# ESP32_C3.net
KiCad netlist of a schematic drawn in Altium Designer
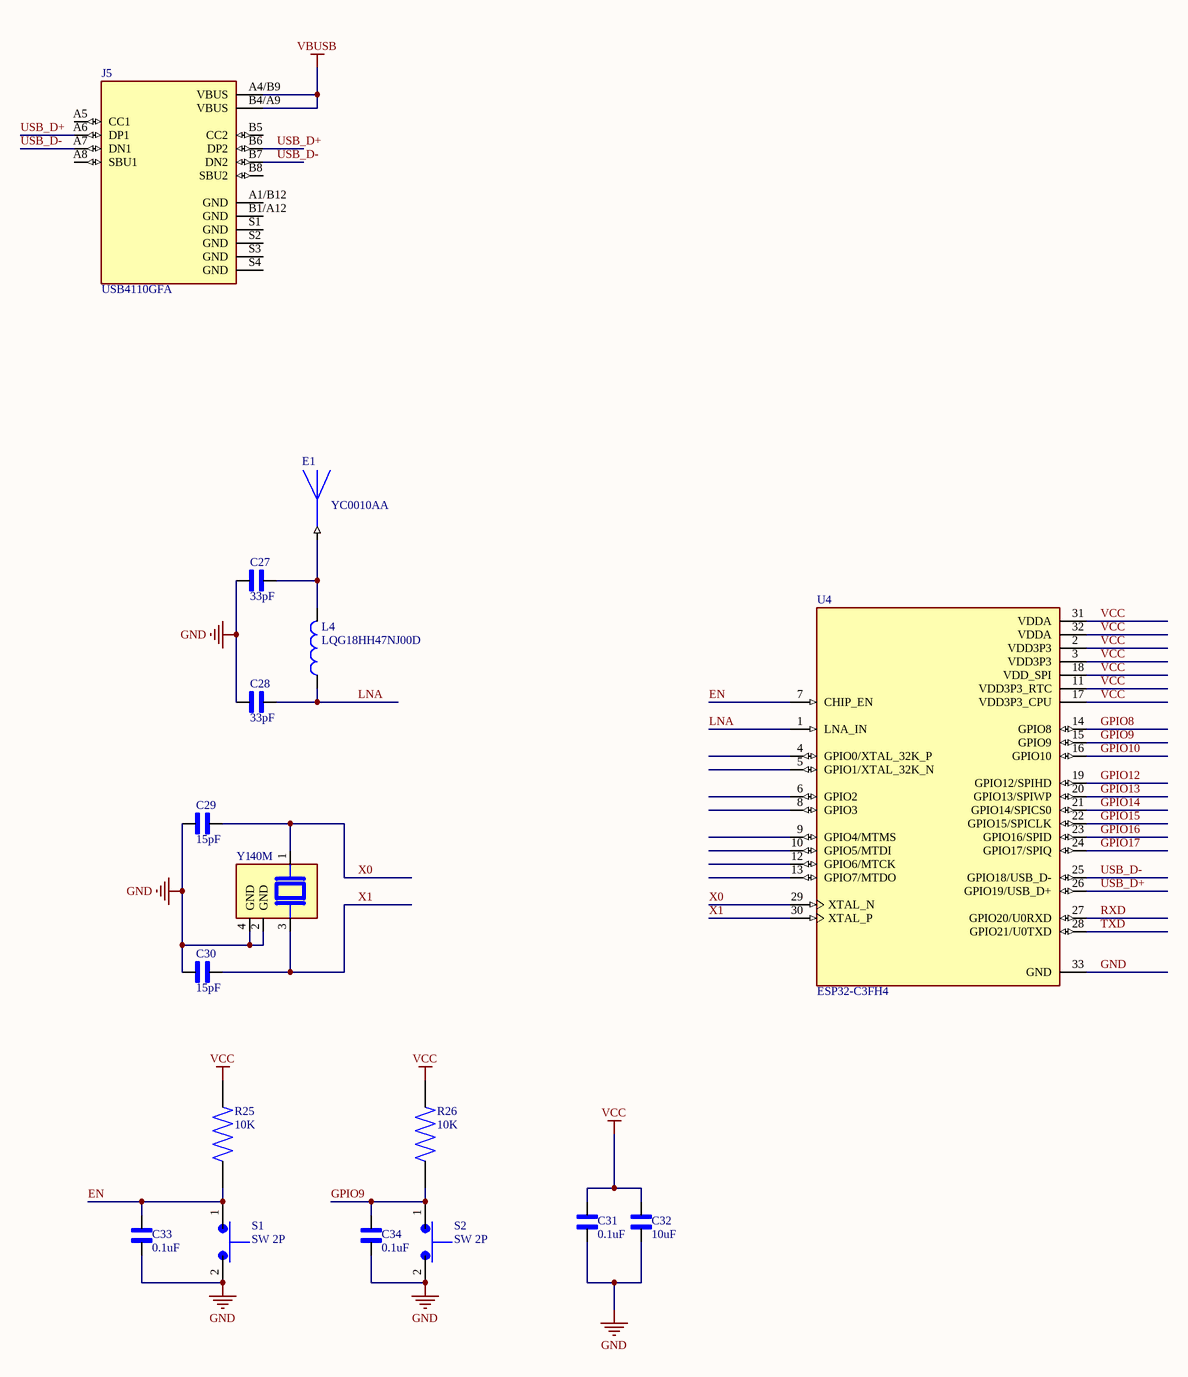
[diagram p0: ESP32 C3.SchDoc]

(export (version "E")
  (design (tool "Eeschema 10.0.6"))
  (components
    (comp (ref "C27")
      (value "33pF")
      (footprint "CAPC2012X140N")
      (fields
        (field (name "MF") "{'manufacturer': u'Samsung Electro-Mechanics'}")
        (field (name "MP") "CL21A226MQQNNNG")
      )
      (libsource (lib "") (part "CL21A226MQQNNNG_1"))
    )
    (comp (ref "C28")
      (value "33pF")
      (footprint "CAPC2012X140N")
      (fields
        (field (name "MF") "{'manufacturer': u'Samsung Electro-Mechanics'}")
        (field (name "MP") "CL21A226MQQNNNG")
      )
      (libsource (lib "") (part "CL21A226MQQNNNG_1"))
    )
    (comp (ref "C29")
      (value "15pF")
      (footprint "CAPC2012X140N")
      (fields
        (field (name "MF") "{'manufacturer': u'Samsung Electro-Mechanics'}")
        (field (name "MP") "CL21A226MQQNNNG")
      )
      (libsource (lib "") (part "CL21A226MQQNNNG_2"))
    )
    (comp (ref "C30")
      (value "15pF")
      (footprint "CAPC2012X140N")
      (fields
        (field (name "MF") "{'manufacturer': u'Samsung Electro-Mechanics'}")
        (field (name "MP") "CL21A226MQQNNNG")
      )
      (libsource (lib "") (part "CL21A226MQQNNNG_1"))
    )
    (comp (ref "C31")
      (value "0.1uF")
      (footprint "CAPC2012X140N")
      (fields
        (field (name "MF") "{'manufacturer': u'Samsung Electro-Mechanics'}")
        (field (name "MP") "CL21A226MQQNNNG")
      )
      (libsource (lib "SnapEDA_Library") (part "CL21A226MQQNNNG"))
    )
    (comp (ref "C32")
      (value "10uF")
      (footprint "CAPC2012X140N")
      (fields
        (field (name "MF") "{'manufacturer': u'Samsung Electro-Mechanics'}")
        (field (name "MP") "CL21A226MQQNNNG")
      )
      (libsource (lib "SnapEDA_Library") (part "CL21A226MQQNNNG"))
    )
    (comp (ref "C33")
      (value "0.1uF")
      (footprint "CAPC2012X140N")
      (fields
        (field (name "MF") "{'manufacturer': u'Samsung Electro-Mechanics'}")
        (field (name "MP") "CL21A226MQQNNNG")
      )
      (libsource (lib "SnapEDA_Library") (part "CL21A226MQQNNNG"))
    )
    (comp (ref "C34")
      (value "0.1uF")
      (footprint "CAPC2012X140N")
      (fields
        (field (name "MF") "{'manufacturer': u'Samsung Electro-Mechanics'}")
        (field (name "MP") "CL21A226MQQNNNG")
      )
      (libsource (lib "SnapEDA_Library") (part "CL21A226MQQNNNG"))
    )
    (comp (ref "E1")
      (value "YC0010AA")
      (footprint "XCVR_YC0010AA")
      (description "2400 ~ 2500MHz, Wi-Fiï¼ˆBTï¼‰, 5.2*2.0*1.2mm,ceramic SMD Antenna")
      (fields (field (name "MF") "Quectel"))
      (libsource (lib "YC0010AA") (part "YC0010AA"))
    )
    (comp (ref "J5")
      (value "USB4110GFA")
      (footprint "GCT_USB4110GFA")
      (fields (field (name "MF") "Global Connector Technology"))
      (libsource (lib "USB4110GFA") (part "USB4110GFA"))
    )
    (comp (ref "L4")
      (value "LQG18HH47NJ00D")
      (footprint "INDC1608X95N")
      (fields (field (name "MF") "{'manufacturer': u'Murata Electronics'}"))
      (libsource (lib "SnapEDA_Library") (part "LQG18HH47NJ00D"))
    )
    (comp (ref "R25")
      (value "10K")
      (footprint "RESC2012X65N")
      (fields (field (name "MF") "{'manufacturer': u'Rohm'}") (field (name "MP") "MCR10EZHJ103"))
      (libsource (lib "SnapEDA_Library") (part "MCR10EZHJ103"))
    )
    (comp (ref "R26")
      (value "10K")
      (footprint "RESC2012X65N")
      (fields (field (name "MF") "{'manufacturer': u'Rohm'}") (field (name "MP") "MCR10EZHJ103"))
      (libsource (lib "SnapEDA_Library") (part "MCR10EZHJ103"))
    )
    (comp (ref "S1")
      (value "SW 2P")
      (footprint "TS10-63-26-BE-250-SMT-TR:SW_TS10-63-26-BE-250-SMT-TR")
      (fields
        (field (name "MF") "{'manufacturer': u'Same Sky'}")
        (field (name "MP") "TS10-63-26-BE-250-SMT-TR")
      )
      (libsource (lib "TS10-63-26-BE-250-SMT-TR") (part "TS10-63-26-BE-250-SMT-TR"))
    )
    (comp (ref "S2")
      (value "SW 2P")
      (footprint "TS10-63-26-BE-250-SMT-TR:SW_TS10-63-26-BE-250-SMT-TR")
      (fields
        (field (name "MF") "{'manufacturer': u'Same Sky'}")
        (field (name "MP") "TS10-63-26-BE-250-SMT-TR")
      )
      (libsource (lib "TS10-63-26-BE-250-SMT-TR") (part "TS10-63-26-BE-250-SMT-TR"))
    )
    (comp (ref "U4")
      (value "ESP32-C3FH4")
      (footprint "QFN50P500X500X90-33N")
      (fields (field (name "MF") "{'manufacturer': u'Espressif Systems'}"))
      (libsource (lib "SnapEDA_Library") (part "ESP32-C3FH4"))
    )
    (comp (ref "Y1")
      (value "40M")
      (footprint "XTAL_ABM12-26.000MHZ-B2X-T3")
      (fields
        (field (name "MF") "{'manufacturer': u'Abracon LLC'}")
        (field (name "MP") "ABM12-26.000MHZ-B2X-T3")
      )
      (libsource (lib "SnapEDA_Library") (part "ABM12-26.000MHZ-B2X-T3"))
    )
  )
  (nets
    (net (code "1") (name "/EN") (class "Default")
      (node (ref "C33") (pin "2") (pinfunction "2_2") (pintype "passive"))
      (node (ref "R25") (pin "1") (pinfunction "1_1") (pintype "passive"))
      (node (ref "S1") (pin "1") (pinfunction "1_1") (pintype "passive"))
      (node (ref "U4") (pin "7") (pinfunction "CHIP_EN_7") (pintype "input"))
    )
    (net (code "2") (name "/GPIO8") (class "Default")
      (node (ref "U4") (pin "14") (pinfunction "GPIO8_14") (pintype "bidirectional"))
    )
    (net (code "3") (name "/GPIO9") (class "Default")
      (node (ref "C34") (pin "2") (pinfunction "2_2") (pintype "passive"))
      (node (ref "R26") (pin "1") (pinfunction "1_1") (pintype "passive"))
      (node (ref "S2") (pin "1") (pinfunction "1_1") (pintype "passive"))
      (node (ref "U4") (pin "15") (pinfunction "GPIO9_15") (pintype "bidirectional"))
    )
    (net (code "4") (name "/GPIO10") (class "Default")
      (node (ref "U4") (pin "16") (pinfunction "GPIO10_16") (pintype "bidirectional"))
    )
    (net (code "5") (name "/GPIO12") (class "Default")
      (node (ref "U4") (pin "19") (pinfunction "GPIO12/SPIHD_19") (pintype "bidirectional"))
    )
    (net (code "6") (name "/GPIO13") (class "Default")
      (node (ref "U4") (pin "20") (pinfunction "GPIO13/SPIWP_20") (pintype "bidirectional"))
    )
    (net (code "7") (name "/GPIO14") (class "Default")
      (node (ref "U4") (pin "21") (pinfunction "GPIO14/SPICS0_21") (pintype "bidirectional"))
    )
    (net (code "8") (name "/GPIO15") (class "Default")
      (node (ref "U4") (pin "22") (pinfunction "GPIO15/SPICLK_22") (pintype "bidirectional"))
    )
    (net (code "9") (name "/GPIO16") (class "Default")
      (node (ref "U4") (pin "23") (pinfunction "GPIO16/SPID_23") (pintype "bidirectional"))
    )
    (net (code "10") (name "/GPIO17") (class "Default")
      (node (ref "U4") (pin "24") (pinfunction "GPIO17/SPIQ_24") (pintype "bidirectional"))
    )
    (net (code "11") (name "/LNA") (class "Default")
      (node (ref "C28") (pin "1") (pinfunction "1_1") (pintype "passive"))
      (node (ref "L4") (pin "1") (pinfunction "1_1") (pintype "passive"))
      (node (ref "U4") (pin "1") (pinfunction "LNA_IN_1") (pintype "input"))
    )
    (net (code "12") (name "/RXD") (class "Default")
      (node (ref "U4") (pin "27") (pinfunction "GPIO20/U0RXD_27") (pintype "bidirectional"))
    )
    (net (code "13") (name "/TXD") (class "Default")
      (node (ref "U4") (pin "28") (pinfunction "GPIO21/U0TXD_28") (pintype "bidirectional"))
    )
    (net (code "14") (name "/USB_D+") (class "Default")
      (node (ref "J5") (pin "A6") (pinfunction "DP1_A6") (pintype "bidirectional"))
      (node (ref "J5") (pin "B6") (pinfunction "DP2_B6") (pintype "bidirectional"))
      (node (ref "U4") (pin "26") (pinfunction "GPIO19/USB_D+_26") (pintype "bidirectional"))
    )
    (net (code "15") (name "/USB_D-") (class "Default")
      (node (ref "J5") (pin "A7") (pinfunction "DN1_A7") (pintype "bidirectional"))
      (node (ref "J5") (pin "B7") (pinfunction "DN2_B7") (pintype "bidirectional"))
      (node (ref "U4") (pin "25") (pinfunction "GPIO18/USB_D-_25") (pintype "bidirectional"))
    )
    (net (code "16") (name "/X0") (class "Default")
      (node (ref "C29") (pin "2") (pinfunction "2_2") (pintype "passive"))
      (node (ref "U4") (pin "29") (pinfunction "XTAL_N_29") (pintype "input"))
      (node (ref "Y1") (pin "1") (pinfunction "1_1") (pintype "passive"))
    )
    (net (code "17") (name "/X1") (class "Default")
      (node (ref "C30") (pin "1") (pinfunction "1_1") (pintype "passive"))
      (node (ref "U4") (pin "30") (pinfunction "XTAL_P_30") (pintype "input"))
      (node (ref "Y1") (pin "3") (pinfunction "2_3") (pintype "passive"))
    )
    (net (code "18") (name "GND") (class "Default")
      (node (ref "C27") (pin "2") (pinfunction "2_2") (pintype "passive"))
      (node (ref "C28") (pin "2") (pinfunction "2_2") (pintype "passive"))
      (node (ref "C29") (pin "1") (pinfunction "1_1") (pintype "passive"))
      (node (ref "C30") (pin "2") (pinfunction "2_2") (pintype "passive"))
      (node (ref "C31") (pin "1") (pinfunction "1_1") (pintype "passive"))
      (node (ref "C32") (pin "1") (pinfunction "1_1") (pintype "passive"))
      (node (ref "C33") (pin "1") (pinfunction "1_1") (pintype "passive"))
      (node (ref "C34") (pin "1") (pinfunction "1_1") (pintype "passive"))
      (node (ref "S1") (pin "2") (pinfunction "2_2") (pintype "passive"))
      (node (ref "S2") (pin "2") (pinfunction "2_2") (pintype "passive"))
      (node (ref "U4") (pin "33") (pinfunction "GND_33") (pintype "power_in"))
      (node (ref "Y1") (pin "2") (pinfunction "GND_2") (pintype "power_in"))
      (node (ref "Y1") (pin "4") (pinfunction "GND_4") (pintype "power_in"))
    )
    (net (code "19") (name "Net-(C27-Pad1)") (class "Default")
      (node (ref "C27") (pin "1") (pinfunction "1_1") (pintype "passive"))
      (node (ref "E1") (pin "1") (pinfunction "1_1") (pintype "input"))
      (node (ref "L4") (pin "2") (pinfunction "2_2") (pintype "passive"))
    )
    (net (code "20") (name "VBUSB") (class "Default")
      (node (ref "J5") (pin "A4/B9") (pinfunction "VBUS_A4/B9") (pintype "power_in"))
      (node (ref "J5") (pin "B4/A9") (pinfunction "VBUS_B4/A9") (pintype "power_in"))
    )
    (net (code "21") (name "VCC") (class "Default")
      (node (ref "C31") (pin "2") (pinfunction "2_2") (pintype "passive"))
      (node (ref "C32") (pin "2") (pinfunction "2_2") (pintype "passive"))
      (node (ref "R25") (pin "2") (pinfunction "2_2") (pintype "passive"))
      (node (ref "R26") (pin "2") (pinfunction "2_2") (pintype "passive"))
      (node (ref "U4") (pin "11") (pinfunction "VDD3P3_RTC_11") (pintype "power_in"))
      (node (ref "U4") (pin "17") (pinfunction "VDD3P3_CPU_17") (pintype "power_in"))
      (node (ref "U4") (pin "18") (pinfunction "VDD_SPI_18") (pintype "power_in"))
      (node (ref "U4") (pin "2") (pinfunction "VDD3P3_2") (pintype "power_in"))
      (node (ref "U4") (pin "3") (pinfunction "VDD3P3_3") (pintype "power_in"))
      (node (ref "U4") (pin "31") (pinfunction "VDDA_31") (pintype "power_in"))
      (node (ref "U4") (pin "32") (pinfunction "VDDA_32") (pintype "power_in"))
    )
    (net (code "22") (name "unconnected-(J5-CC1-PadA5)") (class "Default")
      (node (ref "J5") (pin "A5") (pinfunction "CC1_A5") (pintype "bidirectional"))
    )
    (net (code "23") (name "unconnected-(J5-CC2-PadB5)") (class "Default")
      (node (ref "J5") (pin "B5") (pinfunction "CC2_B5") (pintype "bidirectional"))
    )
    (net (code "24") (name "unconnected-(J5-GND-PadA1{slash}B12)") (class "Default")
      (node (ref "J5") (pin "A1/B12") (pinfunction "GND_A1/B12") (pintype "power_in"))
    )
    (net (code "25") (name "unconnected-(J5-GND-PadB1{slash}A12)") (class "Default")
      (node (ref "J5") (pin "B1/A12") (pinfunction "GND_B1/A12") (pintype "power_in"))
    )
    (net (code "26") (name "unconnected-(J5-GND-PadS1)") (class "Default")
      (node (ref "J5") (pin "S1") (pinfunction "GND_S1") (pintype "power_in"))
    )
    (net (code "27") (name "unconnected-(J5-GND-PadS2)") (class "Default")
      (node (ref "J5") (pin "S2") (pinfunction "GND_S2") (pintype "power_in"))
    )
    (net (code "28") (name "unconnected-(J5-GND-PadS3)") (class "Default")
      (node (ref "J5") (pin "S3") (pinfunction "GND_S3") (pintype "power_in"))
    )
    (net (code "29") (name "unconnected-(J5-GND-PadS4)") (class "Default")
      (node (ref "J5") (pin "S4") (pinfunction "GND_S4") (pintype "power_in"))
    )
    (net (code "30") (name "unconnected-(J5-SBU1-PadA8)") (class "Default")
      (node (ref "J5") (pin "A8") (pinfunction "SBU1_A8") (pintype "bidirectional"))
    )
    (net (code "31") (name "unconnected-(J5-SBU2-PadB8)") (class "Default")
      (node (ref "J5") (pin "B8") (pinfunction "SBU2_B8") (pintype "bidirectional"))
    )
    (net (code "32") (name "unconnected-(U4-GPIO0{slash}XTAL_32K_P-Pad4)") (class "Default")
      (node (ref "U4") (pin "4") (pinfunction "GPIO0/XTAL_32K_P_4") (pintype "bidirectional"))
    )
    (net (code "33") (name "unconnected-(U4-GPIO1{slash}XTAL_32K_N-Pad5)") (class "Default")
      (node (ref "U4") (pin "5") (pinfunction "GPIO1/XTAL_32K_N_5") (pintype "bidirectional"))
    )
    (net (code "34") (name "unconnected-(U4-GPIO2-Pad6)") (class "Default")
      (node (ref "U4") (pin "6") (pinfunction "GPIO2_6") (pintype "bidirectional"))
    )
    (net (code "35") (name "unconnected-(U4-GPIO3-Pad8)") (class "Default")
      (node (ref "U4") (pin "8") (pinfunction "GPIO3_8") (pintype "bidirectional"))
    )
    (net (code "36") (name "unconnected-(U4-GPIO4{slash}MTMS-Pad9)") (class "Default")
      (node (ref "U4") (pin "9") (pinfunction "GPIO4/MTMS_9") (pintype "bidirectional"))
    )
    (net (code "37") (name "unconnected-(U4-GPIO5{slash}MTDI-Pad10)") (class "Default")
      (node (ref "U4") (pin "10") (pinfunction "GPIO5/MTDI_10") (pintype "bidirectional"))
    )
    (net (code "38") (name "unconnected-(U4-GPIO6{slash}MTCK-Pad12)") (class "Default")
      (node (ref "U4") (pin "12") (pinfunction "GPIO6/MTCK_12") (pintype "bidirectional"))
    )
    (net (code "39") (name "unconnected-(U4-GPIO7{slash}MTDO-Pad13)") (class "Default")
      (node (ref "U4") (pin "13") (pinfunction "GPIO7/MTDO_13") (pintype "bidirectional"))
    )
  )
)
